# 8_Channel_Current_Sensor.net
KiCad netlist of a schematic drawn in EAGLE
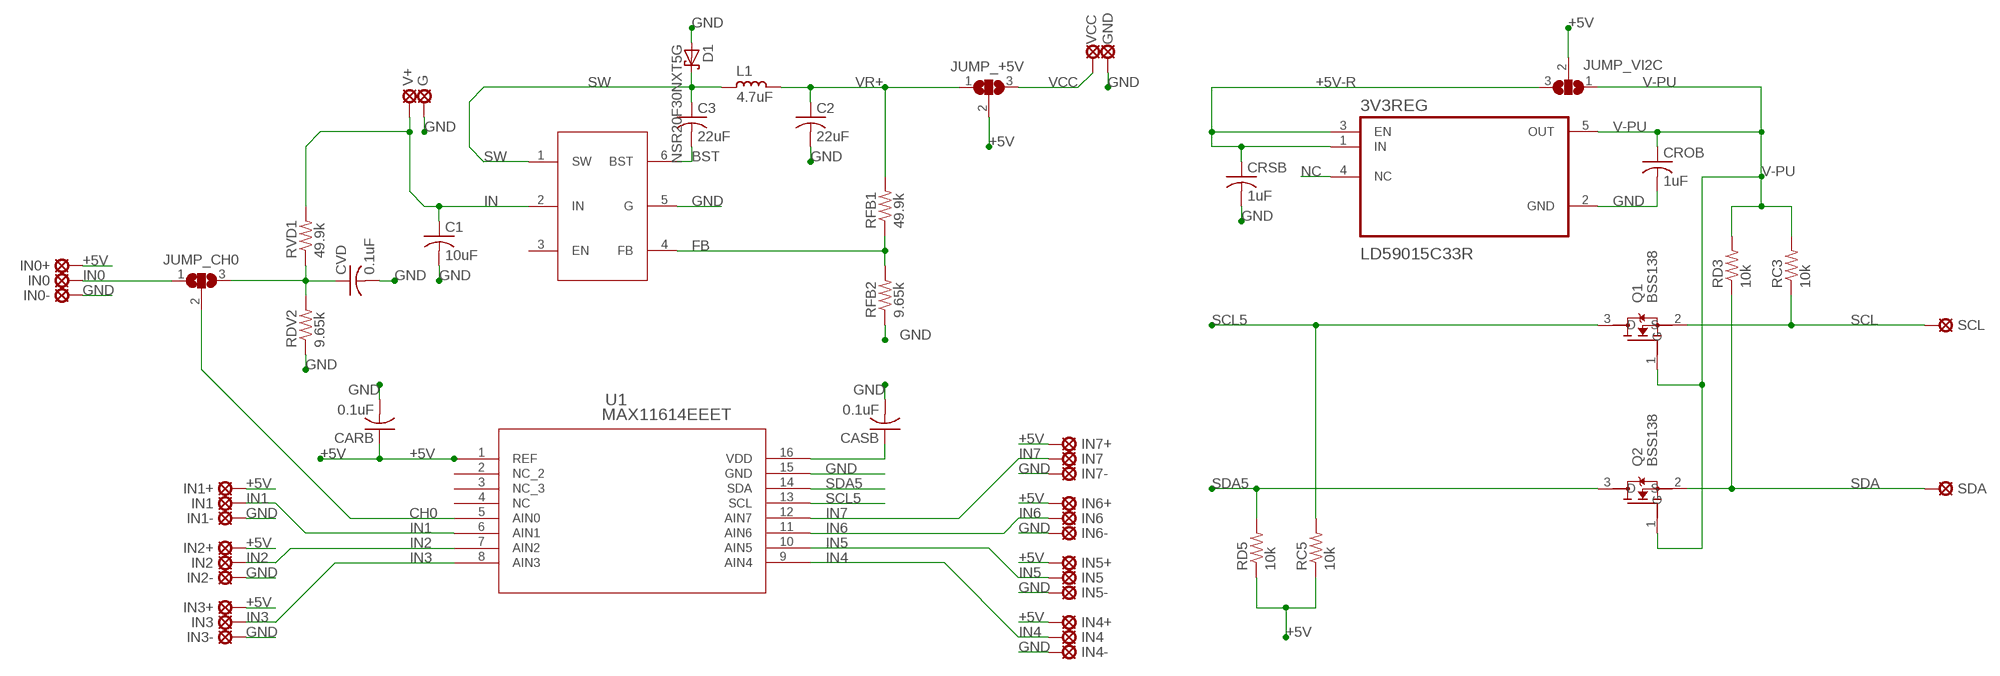
[diagram p0: schematic, sheet 1]

(export (version "E")
  (design (tool "Eeschema 10.0.6"))
  (components
    (comp (ref "3V3REG")
      (value "LD59015C33R")
      (footprint "eagle-import:SOT65P210X110-5N")
      (fields (field (name "MF") "STMicroelectronics"))
      (libsource (lib "eagle-import") (part "LD59015C33R"))
    )
    (comp (ref "5VBUCK")
      (value "ACT4088US-T")
      (footprint "eagle-import:SOT236")
      (libsource (lib "eagle-import") (part "ACT4088US-T"))
    )
    (comp (ref "C1")
      (value "10uF")
      (footprint "eagle-import:C0603K")
      (libsource (lib "eagle-import") (part "C-USC0603K"))
    )
    (comp (ref "C2")
      (value "22uF")
      (footprint "eagle-import:C0603K")
      (libsource (lib "eagle-import") (part "C-USC0603K"))
    )
    (comp (ref "C3")
      (value "22uF")
      (footprint "eagle-import:C0603K")
      (libsource (lib "eagle-import") (part "C-USC0603K"))
    )
    (comp (ref "CARB")
      (value "0.1uF")
      (footprint "eagle-import:C0603")
      (libsource (lib "eagle-import") (part "C-USC0603"))
    )
    (comp (ref "CASB")
      (value "0.1uF")
      (footprint "eagle-import:C0603")
      (libsource (lib "eagle-import") (part "C-USC0603"))
    )
    (comp (ref "CROB")
      (value "1uF")
      (footprint "eagle-import:C0603")
      (libsource (lib "eagle-import") (part "C-USC0603"))
    )
    (comp (ref "CRSB")
      (value "1uF")
      (footprint "eagle-import:C0603")
      (libsource (lib "eagle-import") (part "C-USC0603"))
    )
    (comp (ref "CVD")
      (value "0.1uF")
      (footprint "eagle-import:C0603K")
      (libsource (lib "eagle-import") (part "C-USC0603K"))
    )
    (comp (ref "D1")
      (value "NSR20F30NXT5G")
      (footprint "eagle-import:C0603K")
      (libsource (lib "eagle-import") (part "NSR20F30NXT5G"))
    )
    (comp (ref "G")
      (value "LSP10")
      (footprint "eagle-import:LSP10")
      (libsource (lib "eagle-import") (part "LSP10"))
    )
    (comp (ref "GND")
      (value "LSP10")
      (footprint "eagle-import:LSP10")
      (libsource (lib "eagle-import") (part "LSP10"))
    )
    (comp (ref "IN0")
      (value "LSP10")
      (footprint "eagle-import:LSP10")
      (libsource (lib "eagle-import") (part "LSP10"))
    )
    (comp (ref "IN0+")
      (value "LSP10")
      (footprint "eagle-import:LSP10")
      (libsource (lib "eagle-import") (part "LSP10"))
    )
    (comp (ref "IN0-")
      (value "LSP10")
      (footprint "eagle-import:LSP10")
      (libsource (lib "eagle-import") (part "LSP10"))
    )
    (comp (ref "IN1")
      (value "LSP10")
      (footprint "eagle-import:LSP10")
      (libsource (lib "eagle-import") (part "LSP10"))
    )
    (comp (ref "IN1+")
      (value "LSP10")
      (footprint "eagle-import:LSP10")
      (libsource (lib "eagle-import") (part "LSP10"))
    )
    (comp (ref "IN1-")
      (value "LSP10")
      (footprint "eagle-import:LSP10")
      (libsource (lib "eagle-import") (part "LSP10"))
    )
    (comp (ref "IN2")
      (value "LSP10")
      (footprint "eagle-import:LSP10")
      (libsource (lib "eagle-import") (part "LSP10"))
    )
    (comp (ref "IN2+")
      (value "LSP10")
      (footprint "eagle-import:LSP10")
      (libsource (lib "eagle-import") (part "LSP10"))
    )
    (comp (ref "IN2-")
      (value "LSP10")
      (footprint "eagle-import:LSP10")
      (libsource (lib "eagle-import") (part "LSP10"))
    )
    (comp (ref "IN3")
      (value "LSP10")
      (footprint "eagle-import:LSP10")
      (libsource (lib "eagle-import") (part "LSP10"))
    )
    (comp (ref "IN3+")
      (value "LSP10")
      (footprint "eagle-import:LSP10")
      (libsource (lib "eagle-import") (part "LSP10"))
    )
    (comp (ref "IN3-")
      (value "LSP10")
      (footprint "eagle-import:LSP10")
      (libsource (lib "eagle-import") (part "LSP10"))
    )
    (comp (ref "IN4")
      (value "LSP10")
      (footprint "eagle-import:LSP10")
      (libsource (lib "eagle-import") (part "LSP10"))
    )
    (comp (ref "IN4+")
      (value "LSP10")
      (footprint "eagle-import:LSP10")
      (libsource (lib "eagle-import") (part "LSP10"))
    )
    (comp (ref "IN4-")
      (value "LSP10")
      (footprint "eagle-import:LSP10")
      (libsource (lib "eagle-import") (part "LSP10"))
    )
    (comp (ref "IN5")
      (value "LSP10")
      (footprint "eagle-import:LSP10")
      (libsource (lib "eagle-import") (part "LSP10"))
    )
    (comp (ref "IN5+")
      (value "LSP10")
      (footprint "eagle-import:LSP10")
      (libsource (lib "eagle-import") (part "LSP10"))
    )
    (comp (ref "IN5-")
      (value "LSP10")
      (footprint "eagle-import:LSP10")
      (libsource (lib "eagle-import") (part "LSP10"))
    )
    (comp (ref "IN6")
      (value "LSP10")
      (footprint "eagle-import:LSP10")
      (libsource (lib "eagle-import") (part "LSP10"))
    )
    (comp (ref "IN6+")
      (value "LSP10")
      (footprint "eagle-import:LSP10")
      (libsource (lib "eagle-import") (part "LSP10"))
    )
    (comp (ref "IN6-")
      (value "LSP10")
      (footprint "eagle-import:LSP10")
      (libsource (lib "eagle-import") (part "LSP10"))
    )
    (comp (ref "IN7")
      (value "LSP10")
      (footprint "eagle-import:LSP10")
      (libsource (lib "eagle-import") (part "LSP10"))
    )
    (comp (ref "IN7+")
      (value "LSP10")
      (footprint "eagle-import:LSP10")
      (libsource (lib "eagle-import") (part "LSP10"))
    )
    (comp (ref "IN7-")
      (value "LSP10")
      (footprint "eagle-import:LSP10")
      (libsource (lib "eagle-import") (part "LSP10"))
    )
    (comp (ref "JUMP_+5V")
      (value "SJ2W")
      (footprint "eagle-import:SJ_2")
      (libsource (lib "eagle-import") (part "SJ2W"))
    )
    (comp (ref "JUMP_CH0")
      (value "SJ2W")
      (footprint "eagle-import:SJ_2")
      (libsource (lib "eagle-import") (part "SJ2W"))
    )
    (comp (ref "JUMP_VI2C")
      (value "SJ2W")
      (footprint "eagle-import:SJ_2")
      (libsource (lib "eagle-import") (part "SJ2W"))
    )
    (comp (ref "L1")
      (value "4.7uF")
      (footprint "eagle-import:PM1008")
      (libsource (lib "eagle-import") (part "L_PM1008"))
    )
    (comp (ref "Q1")
      (value "BSS138")
      (footprint "eagle-import:SOT95P240X120-3N")
      (fields (field (name "MF") "ON Semiconductor"))
      (libsource (lib "eagle-import") (part "BSS138"))
    )
    (comp (ref "Q2")
      (value "BSS138")
      (footprint "eagle-import:SOT95P240X120-3N")
      (fields (field (name "MF") "ON Semiconductor"))
      (libsource (lib "eagle-import") (part "BSS138"))
    )
    (comp (ref "RC3")
      (value "10k")
      (footprint "eagle-import:R0603")
      (libsource (lib "eagle-import") (part "R-US_R0603"))
    )
    (comp (ref "RC5")
      (value "10k")
      (footprint "eagle-import:R0603")
      (libsource (lib "eagle-import") (part "R-US_R0603"))
    )
    (comp (ref "RD3")
      (value "10k")
      (footprint "eagle-import:R0603")
      (libsource (lib "eagle-import") (part "R-US_R0603"))
    )
    (comp (ref "RD5")
      (value "10k")
      (footprint "eagle-import:R0603")
      (libsource (lib "eagle-import") (part "R-US_R0603"))
    )
    (comp (ref "RDV2")
      (value "9.65k")
      (footprint "eagle-import:R0603")
      (libsource (lib "eagle-import") (part "R-US_R0603"))
    )
    (comp (ref "RFB1")
      (value "49.9k")
      (footprint "eagle-import:R0603")
      (libsource (lib "eagle-import") (part "R-US_R0603"))
    )
    (comp (ref "RFB2")
      (value "9.65k")
      (footprint "eagle-import:R0603")
      (libsource (lib "eagle-import") (part "R-US_R0603"))
    )
    (comp (ref "RVD1")
      (value "49.9k")
      (footprint "eagle-import:R0603")
      (libsource (lib "eagle-import") (part "R-US_R0603"))
    )
    (comp (ref "SCL")
      (value "LSP10")
      (footprint "eagle-import:LSP10")
      (libsource (lib "eagle-import") (part "LSP10"))
    )
    (comp (ref "SDA")
      (value "LSP10")
      (footprint "eagle-import:LSP10")
      (libsource (lib "eagle-import") (part "LSP10"))
    )
    (comp (ref "U1")
      (value "MAX11614EEET")
      (footprint "eagle-import:21-0055H_16")
      (fields (field (name "MF") "Maxim Integrated") (field (name "MP") "MAX11614EEE+"))
      (libsource (lib "eagle-import") (part "MAX11614EEET"))
    )
    (comp (ref "V+")
      (value "LSP10")
      (footprint "eagle-import:LSP10")
      (libsource (lib "eagle-import") (part "LSP10"))
    )
    (comp (ref "VCC")
      (value "LSP10")
      (footprint "eagle-import:LSP10")
      (libsource (lib "eagle-import") (part "LSP10"))
    )
  )
  (nets
    (net (code "1") (name "/+5V") (class "Default")
      (node (ref "CARB") (pin "1") (pinfunction "1_1") (pintype "passive"))
      (node (ref "CASB") (pin "1") (pinfunction "1_1") (pintype "passive"))
      (node (ref "IN0+") (pin "MP") (pinfunction "MP_MP") (pintype "passive"))
      (node (ref "IN1+") (pin "MP") (pinfunction "MP_MP") (pintype "passive"))
      (node (ref "IN2+") (pin "MP") (pinfunction "MP_MP") (pintype "passive"))
      (node (ref "IN3+") (pin "MP") (pinfunction "MP_MP") (pintype "passive"))
      (node (ref "IN4+") (pin "MP") (pinfunction "MP_MP") (pintype "passive"))
      (node (ref "IN5+") (pin "MP") (pinfunction "MP_MP") (pintype "passive"))
      (node (ref "IN6+") (pin "MP") (pinfunction "MP_MP") (pintype "passive"))
      (node (ref "IN7+") (pin "MP") (pinfunction "MP_MP") (pintype "passive"))
      (node (ref "JUMP_+5V") (pin "2") (pinfunction "2_2") (pintype "passive"))
      (node (ref "JUMP_VI2C") (pin "2") (pinfunction "2_2") (pintype "passive"))
      (node (ref "RC5") (pin "1") (pinfunction "1_1") (pintype "passive"))
      (node (ref "RD5") (pin "1") (pinfunction "1_1") (pintype "passive"))
      (node (ref "U1") (pin "1") (pinfunction "REF_1") (pintype "passive"))
      (node (ref "U1") (pin "16") (pinfunction "VDD_16") (pintype "power_in"))
    )
    (net (code "2") (name "/+5V-R") (class "Default")
      (node (ref "3V3REG") (pin "1") (pinfunction "IN_1") (pintype "input"))
      (node (ref "3V3REG") (pin "3") (pinfunction "EN_3") (pintype "input"))
      (node (ref "CRSB") (pin "1") (pinfunction "1_1") (pintype "passive"))
      (node (ref "JUMP_VI2C") (pin "3") (pinfunction "3_3") (pintype "passive"))
    )
    (net (code "3") (name "/BST") (class "Default")
      (node (ref "5VBUCK") (pin "6") (pinfunction "BST_6") (pintype "input"))
      (node (ref "C3") (pin "2") (pinfunction "2_2") (pintype "passive"))
    )
    (net (code "4") (name "/CH0") (class "Default")
      (node (ref "JUMP_CH0") (pin "2") (pinfunction "2_2") (pintype "passive"))
      (node (ref "U1") (pin "5") (pinfunction "AIN0_5") (pintype "input"))
    )
    (net (code "5") (name "/FB") (class "Default")
      (node (ref "5VBUCK") (pin "4") (pinfunction "FB_4") (pintype "input"))
      (node (ref "RFB1") (pin "1") (pinfunction "1_1") (pintype "passive"))
      (node (ref "RFB2") (pin "2") (pinfunction "2_2") (pintype "passive"))
    )
    (net (code "6") (name "/GND") (class "Default")
      (node (ref "3V3REG") (pin "2") (pinfunction "GND_2") (pintype "power_in"))
      (node (ref "5VBUCK") (pin "5") (pinfunction "G_5") (pintype "power_in"))
      (node (ref "C1") (pin "2") (pinfunction "2_2") (pintype "passive"))
      (node (ref "C2") (pin "2") (pinfunction "2_2") (pintype "passive"))
      (node (ref "CARB") (pin "2") (pinfunction "2_2") (pintype "passive"))
      (node (ref "CASB") (pin "2") (pinfunction "2_2") (pintype "passive"))
      (node (ref "CROB") (pin "2") (pinfunction "2_2") (pintype "passive"))
      (node (ref "CRSB") (pin "2") (pinfunction "2_2") (pintype "passive"))
      (node (ref "CVD") (pin "2") (pinfunction "2_2") (pintype "passive"))
      (node (ref "D1") (pin "1") (pinfunction "A_1") (pintype "passive"))
      (node (ref "G") (pin "MP") (pinfunction "MP_MP") (pintype "passive"))
      (node (ref "GND") (pin "MP") (pinfunction "MP_MP") (pintype "passive"))
      (node (ref "IN0-") (pin "MP") (pinfunction "MP_MP") (pintype "passive"))
      (node (ref "IN1-") (pin "MP") (pinfunction "MP_MP") (pintype "passive"))
      (node (ref "IN2-") (pin "MP") (pinfunction "MP_MP") (pintype "passive"))
      (node (ref "IN3-") (pin "MP") (pinfunction "MP_MP") (pintype "passive"))
      (node (ref "IN4-") (pin "MP") (pinfunction "MP_MP") (pintype "passive"))
      (node (ref "IN5-") (pin "MP") (pinfunction "MP_MP") (pintype "passive"))
      (node (ref "IN6-") (pin "MP") (pinfunction "MP_MP") (pintype "passive"))
      (node (ref "IN7-") (pin "MP") (pinfunction "MP_MP") (pintype "passive"))
      (node (ref "RDV2") (pin "1") (pinfunction "1_1") (pintype "passive"))
      (node (ref "RFB2") (pin "1") (pinfunction "1_1") (pintype "passive"))
      (node (ref "U1") (pin "15") (pinfunction "GND_15") (pintype "power_in"))
    )
    (net (code "7") (name "/IN") (class "Default")
      (node (ref "5VBUCK") (pin "2") (pinfunction "IN_2") (pintype "power_in"))
      (node (ref "C1") (pin "1") (pinfunction "1_1") (pintype "passive"))
      (node (ref "RVD1") (pin "2") (pinfunction "2_2") (pintype "passive"))
      (node (ref "V+") (pin "MP") (pinfunction "MP_MP") (pintype "passive"))
    )
    (net (code "8") (name "/IN0") (class "Default")
      (node (ref "IN0") (pin "MP") (pinfunction "MP_MP") (pintype "passive"))
      (node (ref "JUMP_CH0") (pin "1") (pinfunction "1_1") (pintype "passive"))
    )
    (net (code "9") (name "/IN1") (class "Default")
      (node (ref "IN1") (pin "MP") (pinfunction "MP_MP") (pintype "passive"))
      (node (ref "U1") (pin "6") (pinfunction "AIN1_6") (pintype "input"))
    )
    (net (code "10") (name "/IN2") (class "Default")
      (node (ref "IN2") (pin "MP") (pinfunction "MP_MP") (pintype "passive"))
      (node (ref "U1") (pin "7") (pinfunction "AIN2_7") (pintype "input"))
    )
    (net (code "11") (name "/IN3") (class "Default")
      (node (ref "IN3") (pin "MP") (pinfunction "MP_MP") (pintype "passive"))
      (node (ref "U1") (pin "8") (pinfunction "AIN3_8") (pintype "input"))
    )
    (net (code "12") (name "/IN4") (class "Default")
      (node (ref "IN4") (pin "MP") (pinfunction "MP_MP") (pintype "passive"))
      (node (ref "U1") (pin "9") (pinfunction "AIN4_9") (pintype "input"))
    )
    (net (code "13") (name "/IN5") (class "Default")
      (node (ref "IN5") (pin "MP") (pinfunction "MP_MP") (pintype "passive"))
      (node (ref "U1") (pin "10") (pinfunction "AIN5_10") (pintype "input"))
    )
    (net (code "14") (name "/IN6") (class "Default")
      (node (ref "IN6") (pin "MP") (pinfunction "MP_MP") (pintype "passive"))
      (node (ref "U1") (pin "11") (pinfunction "AIN6_11") (pintype "input"))
    )
    (net (code "15") (name "/IN7") (class "Default")
      (node (ref "IN7") (pin "MP") (pinfunction "MP_MP") (pintype "passive"))
      (node (ref "U1") (pin "12") (pinfunction "AIN7_12") (pintype "input"))
    )
    (net (code "16") (name "/NC") (class "Default")
      (node (ref "3V3REG") (pin "4") (pinfunction "NC_4") (pintype "bidirectional"))
    )
    (net (code "17") (name "/SCL") (class "Default")
      (node (ref "Q1") (pin "2") (pinfunction "S_2") (pintype "passive"))
      (node (ref "RC3") (pin "1") (pinfunction "1_1") (pintype "passive"))
      (node (ref "SCL") (pin "MP") (pinfunction "MP_MP") (pintype "passive"))
    )
    (net (code "18") (name "/SCL5") (class "Default")
      (node (ref "Q1") (pin "3") (pinfunction "D_3") (pintype "passive"))
      (node (ref "RC5") (pin "2") (pinfunction "2_2") (pintype "passive"))
      (node (ref "U1") (pin "13") (pinfunction "SCL_13") (pintype "passive"))
    )
    (net (code "19") (name "/SDA") (class "Default")
      (node (ref "Q2") (pin "2") (pinfunction "S_2") (pintype "passive"))
      (node (ref "RD3") (pin "1") (pinfunction "1_1") (pintype "passive"))
      (node (ref "SDA") (pin "MP") (pinfunction "MP_MP") (pintype "passive"))
    )
    (net (code "20") (name "/SDA5") (class "Default")
      (node (ref "Q2") (pin "3") (pinfunction "D_3") (pintype "passive"))
      (node (ref "RD5") (pin "2") (pinfunction "2_2") (pintype "passive"))
      (node (ref "U1") (pin "14") (pinfunction "SDA_14") (pintype "passive"))
    )
    (net (code "21") (name "/SW") (class "Default")
      (node (ref "5VBUCK") (pin "1") (pinfunction "SW_1") (pintype "output"))
      (node (ref "C3") (pin "1") (pinfunction "1_1") (pintype "passive"))
      (node (ref "D1") (pin "2") (pinfunction "C_2") (pintype "passive"))
      (node (ref "L1") (pin "2") (pinfunction "2_2") (pintype "passive"))
    )
    (net (code "22") (name "/V-PU") (class "Default")
      (node (ref "3V3REG") (pin "5") (pinfunction "OUT_5") (pintype "output"))
      (node (ref "CROB") (pin "1") (pinfunction "1_1") (pintype "passive"))
      (node (ref "JUMP_VI2C") (pin "1") (pinfunction "1_1") (pintype "passive"))
      (node (ref "Q1") (pin "1") (pinfunction "G_1") (pintype "passive"))
      (node (ref "Q2") (pin "1") (pinfunction "G_1") (pintype "passive"))
      (node (ref "RC3") (pin "2") (pinfunction "2_2") (pintype "passive"))
      (node (ref "RD3") (pin "2") (pinfunction "2_2") (pintype "passive"))
    )
    (net (code "23") (name "/VCC") (class "Default")
      (node (ref "JUMP_+5V") (pin "3") (pinfunction "3_3") (pintype "passive"))
      (node (ref "VCC") (pin "MP") (pinfunction "MP_MP") (pintype "passive"))
    )
    (net (code "24") (name "/VR+") (class "Default")
      (node (ref "C2") (pin "1") (pinfunction "1_1") (pintype "passive"))
      (node (ref "JUMP_+5V") (pin "1") (pinfunction "1_1") (pintype "passive"))
      (node (ref "L1") (pin "1") (pinfunction "1_1") (pintype "passive"))
      (node (ref "RFB1") (pin "2") (pinfunction "2_2") (pintype "passive"))
    )
    (net (code "25") (name "Net-(CVD-Pad1)") (class "Default")
      (node (ref "CVD") (pin "1") (pinfunction "1_1") (pintype "passive"))
      (node (ref "JUMP_CH0") (pin "3") (pinfunction "3_3") (pintype "passive"))
      (node (ref "RDV2") (pin "2") (pinfunction "2_2") (pintype "passive"))
      (node (ref "RVD1") (pin "1") (pinfunction "1_1") (pintype "passive"))
    )
    (net (code "26") (name "unconnected-(5VBUCK-EN-Pad3)") (class "Default")
      (node (ref "5VBUCK") (pin "3") (pinfunction "EN_3") (pintype "input"))
    )
    (net (code "27") (name "unconnected-(U1-NC-Pad4)") (class "Default")
      (node (ref "U1") (pin "4") (pinfunction "NC_4") (pintype "passive"))
    )
    (net (code "28") (name "unconnected-(U1-NC_2-Pad2)") (class "Default")
      (node (ref "U1") (pin "2") (pinfunction "NC_2_2") (pintype "passive"))
    )
    (net (code "29") (name "unconnected-(U1-NC_3-Pad3)") (class "Default")
      (node (ref "U1") (pin "3") (pinfunction "NC_3_3") (pintype "passive"))
    )
  )
)
